# DetectionPart.net
KiCad netlist of a schematic drawn in Altium Designer
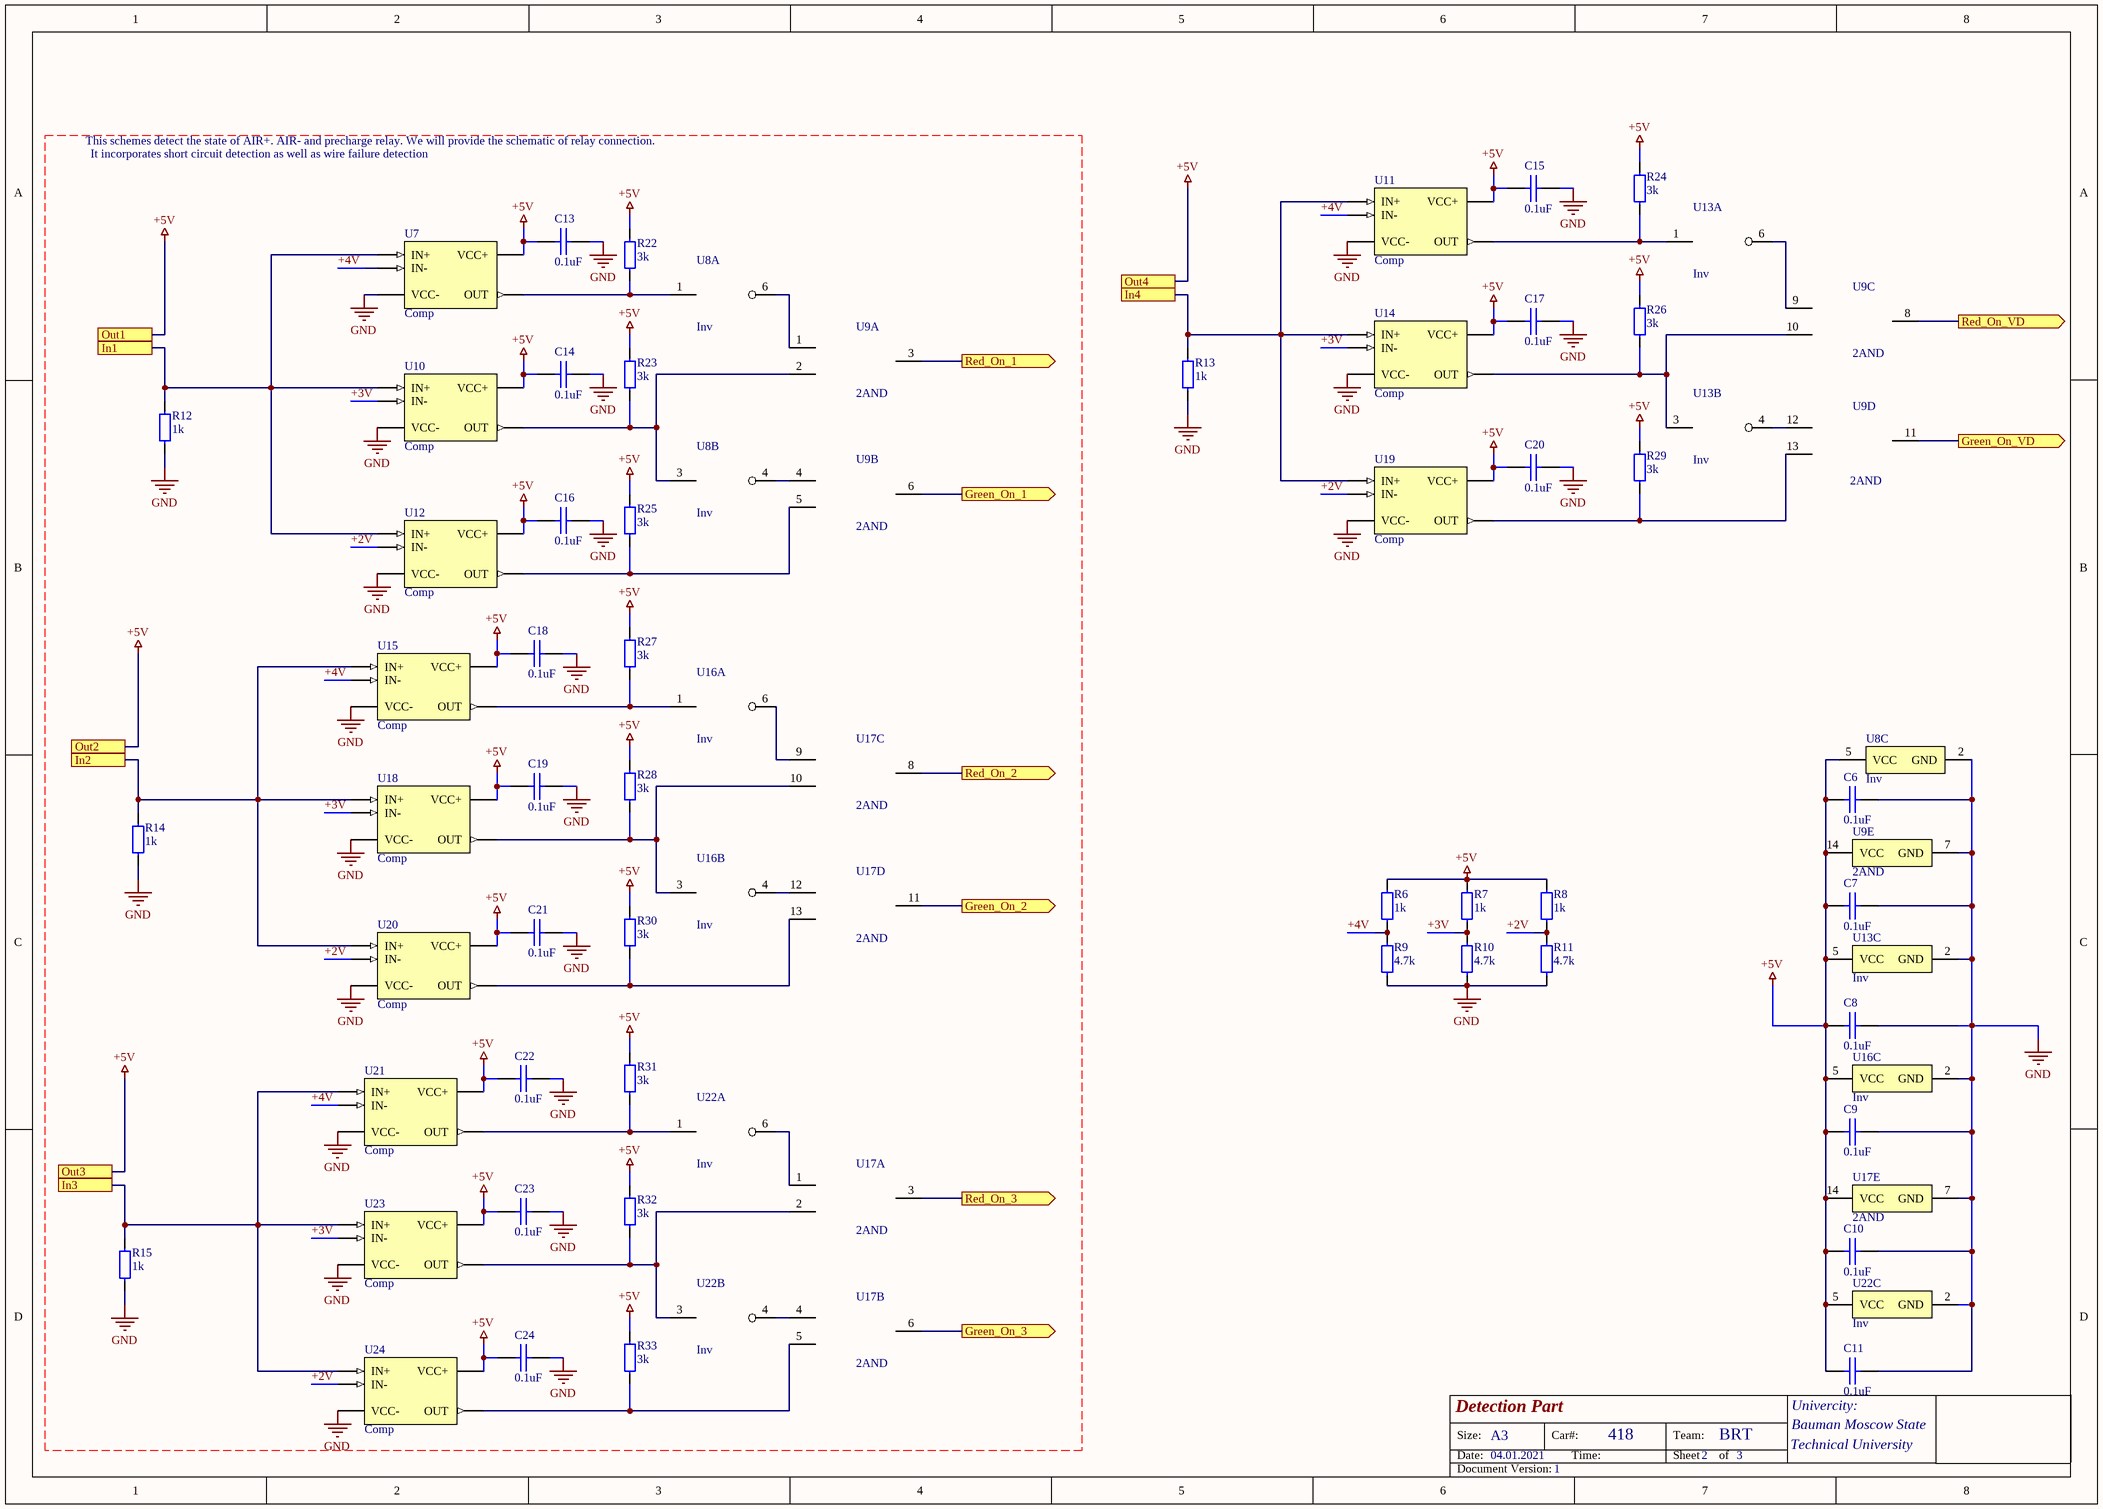
[diagram p0: DetectionPart.SchDoc]

(export (version "E")
  (design (tool "Eeschema 10.0.6"))
  (components
    (comp (ref "C6")
      (value "0.1uF")
      (footprint "0603 Capicator")
      (description "0.1uF X7R 16V 10% 0603")
      (fields
        (field (name "MANUFACTURER") "Murata Manufacturing")
        (field (name "PART NUMBER") "GRM188R71C104KA01D")
      )
      (libsource (lib "BRT_Components") (part "Cap 0.1uF (0603)"))
    )
    (comp (ref "C7")
      (value "0.1uF")
      (footprint "0603 Capicator")
      (description "0.1uF X7R 16V 10% 0603")
      (fields
        (field (name "MANUFACTURER") "Murata Manufacturing")
        (field (name "PART NUMBER") "GRM188R71C104KA01D")
      )
      (libsource (lib "BRT_Components") (part "Cap 0.1uF (0603)"))
    )
    (comp (ref "C8")
      (value "0.1uF")
      (footprint "0603 Capicator")
      (description "0.1uF X7R 16V 10% 0603")
      (fields
        (field (name "MANUFACTURER") "Murata Manufacturing")
        (field (name "PART NUMBER") "GRM188R71C104KA01D")
      )
      (libsource (lib "BRT_Components") (part "Cap 0.1uF (0603)"))
    )
    (comp (ref "C9")
      (value "0.1uF")
      (footprint "0603 Capicator")
      (description "0.1uF X7R 16V 10% 0603")
      (fields
        (field (name "MANUFACTURER") "Murata Manufacturing")
        (field (name "PART NUMBER") "GRM188R71C104KA01D")
      )
      (libsource (lib "BRT_Components") (part "Cap 0.1uF (0603)"))
    )
    (comp (ref "C10")
      (value "0.1uF")
      (footprint "0603 Capicator")
      (description "0.1uF X7R 16V 10% 0603")
      (fields
        (field (name "MANUFACTURER") "Murata Manufacturing")
        (field (name "PART NUMBER") "GRM188R71C104KA01D")
      )
      (libsource (lib "BRT_Components") (part "Cap 0.1uF (0603)"))
    )
    (comp (ref "C11")
      (value "0.1uF")
      (footprint "0603 Capicator")
      (description "0.1uF X7R 16V 10% 0603")
      (fields
        (field (name "MANUFACTURER") "Murata Manufacturing")
        (field (name "PART NUMBER") "GRM188R71C104KA01D")
      )
      (libsource (lib "BRT_Components") (part "Cap 0.1uF (0603)"))
    )
    (comp (ref "C13")
      (value "0.1uF")
      (footprint "0603 Capicator")
      (description "0.1uF X7R 16V 10% 0603")
      (fields
        (field (name "MANUFACTURER") "Murata Manufacturing")
        (field (name "PART NUMBER") "GRM188R71C104KA01D")
      )
      (libsource (lib "BRT_Components") (part "Cap 0.1uF (0603)"))
    )
    (comp (ref "C14")
      (value "0.1uF")
      (footprint "0603 Capicator")
      (description "0.1uF X7R 16V 10% 0603")
      (fields
        (field (name "MANUFACTURER") "Murata Manufacturing")
        (field (name "PART NUMBER") "GRM188R71C104KA01D")
      )
      (libsource (lib "BRT_Components") (part "Cap 0.1uF (0603)"))
    )
    (comp (ref "C15")
      (value "0.1uF")
      (footprint "0603 Capicator")
      (description "0.1uF X7R 16V 10% 0603")
      (fields
        (field (name "MANUFACTURER") "Murata Manufacturing")
        (field (name "PART NUMBER") "GRM188R71C104KA01D")
      )
      (libsource (lib "BRT_Components") (part "Cap 0.1uF (0603)"))
    )
    (comp (ref "C16")
      (value "0.1uF")
      (footprint "0603 Capicator")
      (description "0.1uF X7R 16V 10% 0603")
      (fields
        (field (name "MANUFACTURER") "Murata Manufacturing")
        (field (name "PART NUMBER") "GRM188R71C104KA01D")
      )
      (libsource (lib "BRT_Components") (part "Cap 0.1uF (0603)"))
    )
    (comp (ref "C17")
      (value "0.1uF")
      (footprint "0603 Capicator")
      (description "0.1uF X7R 16V 10% 0603")
      (fields
        (field (name "MANUFACTURER") "Murata Manufacturing")
        (field (name "PART NUMBER") "GRM188R71C104KA01D")
      )
      (libsource (lib "BRT_Components") (part "Cap 0.1uF (0603)"))
    )
    (comp (ref "C18")
      (value "0.1uF")
      (footprint "0603 Capicator")
      (description "0.1uF X7R 16V 10% 0603")
      (fields
        (field (name "MANUFACTURER") "Murata Manufacturing")
        (field (name "PART NUMBER") "GRM188R71C104KA01D")
      )
      (libsource (lib "BRT_Components") (part "Cap 0.1uF (0603)"))
    )
    (comp (ref "C19")
      (value "0.1uF")
      (footprint "0603 Capicator")
      (description "0.1uF X7R 16V 10% 0603")
      (fields
        (field (name "MANUFACTURER") "Murata Manufacturing")
        (field (name "PART NUMBER") "GRM188R71C104KA01D")
      )
      (libsource (lib "BRT_Components") (part "Cap 0.1uF (0603)"))
    )
    (comp (ref "C20")
      (value "0.1uF")
      (footprint "0603 Capicator")
      (description "0.1uF X7R 16V 10% 0603")
      (fields
        (field (name "MANUFACTURER") "Murata Manufacturing")
        (field (name "PART NUMBER") "GRM188R71C104KA01D")
      )
      (libsource (lib "BRT_Components") (part "Cap 0.1uF (0603)"))
    )
    (comp (ref "C21")
      (value "0.1uF")
      (footprint "0603 Capicator")
      (description "0.1uF X7R 16V 10% 0603")
      (fields
        (field (name "MANUFACTURER") "Murata Manufacturing")
        (field (name "PART NUMBER") "GRM188R71C104KA01D")
      )
      (libsource (lib "BRT_Components") (part "Cap 0.1uF (0603)"))
    )
    (comp (ref "C22")
      (value "0.1uF")
      (footprint "0603 Capicator")
      (description "0.1uF X7R 16V 10% 0603")
      (fields
        (field (name "MANUFACTURER") "Murata Manufacturing")
        (field (name "PART NUMBER") "GRM188R71C104KA01D")
      )
      (libsource (lib "BRT_Components") (part "Cap 0.1uF (0603)"))
    )
    (comp (ref "C23")
      (value "0.1uF")
      (footprint "0603 Capicator")
      (description "0.1uF X7R 16V 10% 0603")
      (fields
        (field (name "MANUFACTURER") "Murata Manufacturing")
        (field (name "PART NUMBER") "GRM188R71C104KA01D")
      )
      (libsource (lib "BRT_Components") (part "Cap 0.1uF (0603)"))
    )
    (comp (ref "C24")
      (value "0.1uF")
      (footprint "0603 Capicator")
      (description "0.1uF X7R 16V 10% 0603")
      (fields
        (field (name "MANUFACTURER") "Murata Manufacturing")
        (field (name "PART NUMBER") "GRM188R71C104KA01D")
      )
      (libsource (lib "BRT_Components") (part "Cap 0.1uF (0603)"))
    )
    (comp (ref "R6")
      (value "1k")
      (footprint "0603 Resistor")
      (description "0.1W 0603 1k, 1%")
      (fields (field (name "PART NUMBER") "RC0603FR-071KL") (field (name "MANUFACTURER") "Taiwan"))
      (libsource (lib "BRT_Components") (part "Res 1k (0603)"))
    )
    (comp (ref "R7")
      (value "1k")
      (footprint "0603 Resistor")
      (description "0.1W 0603 1k, 1%")
      (fields (field (name "PART NUMBER") "RC0603FR-071KL") (field (name "MANUFACTURER") "Taiwan"))
      (libsource (lib "BRT_Components") (part "Res 1k (0603)"))
    )
    (comp (ref "R8")
      (value "1k")
      (footprint "0603 Resistor")
      (description "0.1W 0603 1k, 1%")
      (fields (field (name "PART NUMBER") "RC0603FR-071KL") (field (name "MANUFACTURER") "Taiwan"))
      (libsource (lib "BRT_Components") (part "Res 1k (0603)"))
    )
    (comp (ref "R9")
      (value "4.7k")
      (footprint "0603 Resistor")
      (description "0.1W 0603 4.7k, 1%")
      (fields (field (name "PART NUMBER") "RC0603FR-074K7L") (field (name "MANUFACTURER") "Taiwan"))
      (libsource (lib "BRT_Components") (part "Res 4.7k (0603)"))
    )
    (comp (ref "R10")
      (value "4.7k")
      (footprint "0603 Resistor")
      (description "0.1W 0603 4.7k, 1%")
      (fields (field (name "PART NUMBER") "RC0603FR-074K7L") (field (name "MANUFACTURER") "Taiwan"))
      (libsource (lib "BRT_Components") (part "Res 4.7k (0603)"))
    )
    (comp (ref "R11")
      (value "4.7k")
      (footprint "0603 Resistor")
      (description "0.1W 0603 4.7k, 1%")
      (fields (field (name "PART NUMBER") "RC0603FR-074K7L") (field (name "MANUFACTURER") "Taiwan"))
      (libsource (lib "BRT_Components") (part "Res 4.7k (0603)"))
    )
    (comp (ref "R12")
      (value "1k")
      (footprint "0603 Resistor")
      (description "0.1W 0603 1k, 1%")
      (fields (field (name "PART NUMBER") "RC0603FR-071KL") (field (name "MANUFACTURER") "Taiwan"))
      (libsource (lib "BRT_Components") (part "Res 1k (0603)"))
    )
    (comp (ref "R13")
      (value "1k")
      (footprint "0603 Resistor")
      (description "0.1W 0603 1k, 1%")
      (fields (field (name "PART NUMBER") "RC0603FR-071KL") (field (name "MANUFACTURER") "Taiwan"))
      (libsource (lib "BRT_Components") (part "Res 1k (0603)"))
    )
    (comp (ref "R14")
      (value "1k")
      (footprint "0603 Resistor")
      (description "0.1W 0603 1k, 1%")
      (fields (field (name "PART NUMBER") "RC0603FR-071KL") (field (name "MANUFACTURER") "Taiwan"))
      (libsource (lib "BRT_Components") (part "Res 1k (0603)"))
    )
    (comp (ref "R15")
      (value "1k")
      (footprint "0603 Resistor")
      (description "0.1W 0603 1k, 1%")
      (fields (field (name "PART NUMBER") "RC0603FR-071KL") (field (name "MANUFACTURER") "Taiwan"))
      (libsource (lib "BRT_Components") (part "Res 1k (0603)"))
    )
    (comp (ref "R22")
      (value "3k")
      (footprint "0603 Resistor")
      (description "0.1W 0603 3k, 1%")
      (fields (field (name "PART NUMBER") "RC0603FR-073KL") (field (name "MANUFACTURER") "Taiwan"))
      (libsource (lib "BRT_Components") (part "Res 3k (0603)"))
    )
    (comp (ref "R23")
      (value "3k")
      (footprint "0603 Resistor")
      (description "0.1W 0603 3k, 1%")
      (fields (field (name "PART NUMBER") "RC0603FR-073KL") (field (name "MANUFACTURER") "Taiwan"))
      (libsource (lib "BRT_Components") (part "Res 3k (0603)"))
    )
    (comp (ref "R24")
      (value "3k")
      (footprint "0603 Resistor")
      (description "0.1W 0603 3k, 1%")
      (fields (field (name "PART NUMBER") "RC0603FR-073KL") (field (name "MANUFACTURER") "Taiwan"))
      (libsource (lib "BRT_Components") (part "Res 3k (0603)"))
    )
    (comp (ref "R25")
      (value "3k")
      (footprint "0603 Resistor")
      (description "0.1W 0603 3k, 1%")
      (fields (field (name "PART NUMBER") "RC0603FR-073KL") (field (name "MANUFACTURER") "Taiwan"))
      (libsource (lib "BRT_Components") (part "Res 3k (0603)"))
    )
    (comp (ref "R26")
      (value "3k")
      (footprint "0603 Resistor")
      (description "0.1W 0603 3k, 1%")
      (fields (field (name "PART NUMBER") "RC0603FR-073KL") (field (name "MANUFACTURER") "Taiwan"))
      (libsource (lib "BRT_Components") (part "Res 3k (0603)"))
    )
    (comp (ref "R27")
      (value "3k")
      (footprint "0603 Resistor")
      (description "0.1W 0603 3k, 1%")
      (fields (field (name "PART NUMBER") "RC0603FR-073KL") (field (name "MANUFACTURER") "Taiwan"))
      (libsource (lib "BRT_Components") (part "Res 3k (0603)"))
    )
    (comp (ref "R28")
      (value "3k")
      (footprint "0603 Resistor")
      (description "0.1W 0603 3k, 1%")
      (fields (field (name "PART NUMBER") "RC0603FR-073KL") (field (name "MANUFACTURER") "Taiwan"))
      (libsource (lib "BRT_Components") (part "Res 3k (0603)"))
    )
    (comp (ref "R29")
      (value "3k")
      (footprint "0603 Resistor")
      (description "0.1W 0603 3k, 1%")
      (fields (field (name "PART NUMBER") "RC0603FR-073KL") (field (name "MANUFACTURER") "Taiwan"))
      (libsource (lib "BRT_Components") (part "Res 3k (0603)"))
    )
    (comp (ref "R30")
      (value "3k")
      (footprint "0603 Resistor")
      (description "0.1W 0603 3k, 1%")
      (fields (field (name "PART NUMBER") "RC0603FR-073KL") (field (name "MANUFACTURER") "Taiwan"))
      (libsource (lib "BRT_Components") (part "Res 3k (0603)"))
    )
    (comp (ref "R31")
      (value "3k")
      (footprint "0603 Resistor")
      (description "0.1W 0603 3k, 1%")
      (fields (field (name "PART NUMBER") "RC0603FR-073KL") (field (name "MANUFACTURER") "Taiwan"))
      (libsource (lib "BRT_Components") (part "Res 3k (0603)"))
    )
    (comp (ref "R32")
      (value "3k")
      (footprint "0603 Resistor")
      (description "0.1W 0603 3k, 1%")
      (fields (field (name "PART NUMBER") "RC0603FR-073KL") (field (name "MANUFACTURER") "Taiwan"))
      (libsource (lib "BRT_Components") (part "Res 3k (0603)"))
    )
    (comp (ref "R33")
      (value "3k")
      (footprint "0603 Resistor")
      (description "0.1W 0603 3k, 1%")
      (fields (field (name "PART NUMBER") "RC0603FR-073KL") (field (name "MANUFACTURER") "Taiwan"))
      (libsource (lib "BRT_Components") (part "Res 3k (0603)"))
    )
    (comp (ref "U7")
      (value "Comp")
      (footprint "SOT-23-5")
      (description "Differential comparator with strobes")
      (fields (field (name "PART NUMBER") "LMV331M5/NOPB") (field (name "MANUFACTURER") "Texas Instruments"))
      (libsource (lib "BRT_Components") (part "Comparator [LMV]"))
    )
    (comp (ref "U8")
      (value "Inv")
      (footprint "SOT236")
      (description "Dual inverter, 1.65-5.5V")
      (fields
        (field (name "MANUFACTURER") "Texas Instruments")
        (field (name "PART NUMBER") "SN74LVC2G04DBVR")
      )
      (libsource (lib "BRT_Components") (part "Inverter (SN74)"))
    )
    (comp (ref "U9")
      (value "2AND")
      (footprint "SOIC-14")
      (description "4 logic elements \"2AND\"")
      (fields (field (name "PART NUMBER") "SN74AC08DR") (field (name "MANUFACTURER") "Texas Instruments"))
      (libsource (lib "BRT_Components") (part "2And"))
    )
    (comp (ref "U10")
      (value "Comp")
      (footprint "SOT-23-5")
      (description "Differential comparator with strobes")
      (fields (field (name "PART NUMBER") "LMV331M5/NOPB") (field (name "MANUFACTURER") "Texas Instruments"))
      (libsource (lib "BRT_Components") (part "Comparator [LMV]"))
    )
    (comp (ref "U11")
      (value "Comp")
      (footprint "SOT-23-5")
      (description "Differential comparator with strobes")
      (fields (field (name "PART NUMBER") "LMV331M5/NOPB") (field (name "MANUFACTURER") "Texas Instruments"))
      (libsource (lib "BRT_Components") (part "Comparator [LMV]"))
    )
    (comp (ref "U12")
      (value "Comp")
      (footprint "SOT-23-5")
      (description "Differential comparator with strobes")
      (fields (field (name "PART NUMBER") "LMV331M5/NOPB") (field (name "MANUFACTURER") "Texas Instruments"))
      (libsource (lib "BRT_Components") (part "Comparator [LMV]"))
    )
    (comp (ref "U13")
      (value "Inv")
      (footprint "SOT236")
      (description "Dual inverter, 1.65-5.5V")
      (fields
        (field (name "MANUFACTURER") "Texas Instruments")
        (field (name "PART NUMBER") "SN74LVC2G04DBVR")
      )
      (libsource (lib "BRT_Components") (part "Inverter (SN74)"))
    )
    (comp (ref "U14")
      (value "Comp")
      (footprint "SOT-23-5")
      (description "Differential comparator with strobes")
      (fields (field (name "PART NUMBER") "LMV331M5/NOPB") (field (name "MANUFACTURER") "Texas Instruments"))
      (libsource (lib "BRT_Components") (part "Comparator [LMV]"))
    )
    (comp (ref "U15")
      (value "Comp")
      (footprint "SOT-23-5")
      (description "Differential comparator with strobes")
      (fields (field (name "PART NUMBER") "LMV331M5/NOPB") (field (name "MANUFACTURER") "Texas Instruments"))
      (libsource (lib "BRT_Components") (part "Comparator [LMV]"))
    )
    (comp (ref "U16")
      (value "Inv")
      (footprint "SOT236")
      (description "Dual inverter, 1.65-5.5V")
      (fields
        (field (name "MANUFACTURER") "Texas Instruments")
        (field (name "PART NUMBER") "SN74LVC2G04DBVR")
      )
      (libsource (lib "BRT_Components") (part "Inverter (SN74)"))
    )
    (comp (ref "U17")
      (value "2AND")
      (footprint "SOIC-14")
      (description "4 logic elements \"2AND\"")
      (fields (field (name "PART NUMBER") "SN74AC08DR") (field (name "MANUFACTURER") "Texas Instruments"))
      (libsource (lib "BRT_Components") (part "2And"))
    )
    (comp (ref "U18")
      (value "Comp")
      (footprint "SOT-23-5")
      (description "Differential comparator with strobes")
      (fields (field (name "PART NUMBER") "LMV331M5/NOPB") (field (name "MANUFACTURER") "Texas Instruments"))
      (libsource (lib "BRT_Components") (part "Comparator [LMV]"))
    )
    (comp (ref "U19")
      (value "Comp")
      (footprint "SOT-23-5")
      (description "Differential comparator with strobes")
      (fields (field (name "PART NUMBER") "LMV331M5/NOPB") (field (name "MANUFACTURER") "Texas Instruments"))
      (libsource (lib "BRT_Components") (part "Comparator [LMV]"))
    )
    (comp (ref "U20")
      (value "Comp")
      (footprint "SOT-23-5")
      (description "Differential comparator with strobes")
      (fields (field (name "PART NUMBER") "LMV331M5/NOPB") (field (name "MANUFACTURER") "Texas Instruments"))
      (libsource (lib "BRT_Components") (part "Comparator [LMV]"))
    )
    (comp (ref "U21")
      (value "Comp")
      (footprint "SOT-23-5")
      (description "Differential comparator with strobes")
      (fields (field (name "PART NUMBER") "LMV331M5/NOPB") (field (name "MANUFACTURER") "Texas Instruments"))
      (libsource (lib "BRT_Components") (part "Comparator [LMV]"))
    )
    (comp (ref "U22")
      (value "Inv")
      (footprint "SOT236")
      (description "Dual inverter, 1.65-5.5V")
      (fields
        (field (name "MANUFACTURER") "Texas Instruments")
        (field (name "PART NUMBER") "SN74LVC2G04DBVR")
      )
      (libsource (lib "BRT_Components") (part "Inverter (SN74)"))
    )
    (comp (ref "U23")
      (value "Comp")
      (footprint "SOT-23-5")
      (description "Differential comparator with strobes")
      (fields (field (name "PART NUMBER") "LMV331M5/NOPB") (field (name "MANUFACTURER") "Texas Instruments"))
      (libsource (lib "BRT_Components") (part "Comparator [LMV]"))
    )
    (comp (ref "U24")
      (value "Comp")
      (footprint "SOT-23-5")
      (description "Differential comparator with strobes")
      (fields (field (name "PART NUMBER") "LMV331M5/NOPB") (field (name "MANUFACTURER") "Texas Instruments"))
      (libsource (lib "BRT_Components") (part "Comparator [LMV]"))
    )
  )
  (nets
    (net (code "1") (name "+5V") (class "Default")
      (node (ref "C10") (pin "2") (pinfunction "2_2") (pintype "passive"))
      (node (ref "C11") (pin "2") (pinfunction "2_2") (pintype "passive"))
      (node (ref "C13") (pin "2") (pinfunction "2_2") (pintype "passive"))
      (node (ref "C14") (pin "2") (pinfunction "2_2") (pintype "passive"))
      (node (ref "C15") (pin "2") (pinfunction "2_2") (pintype "passive"))
      (node (ref "C16") (pin "2") (pinfunction "2_2") (pintype "passive"))
      (node (ref "C17") (pin "2") (pinfunction "2_2") (pintype "passive"))
      (node (ref "C18") (pin "2") (pinfunction "2_2") (pintype "passive"))
      (node (ref "C19") (pin "2") (pinfunction "2_2") (pintype "passive"))
      (node (ref "C20") (pin "2") (pinfunction "2_2") (pintype "passive"))
      (node (ref "C21") (pin "2") (pinfunction "2_2") (pintype "passive"))
      (node (ref "C22") (pin "2") (pinfunction "2_2") (pintype "passive"))
      (node (ref "C23") (pin "2") (pinfunction "2_2") (pintype "passive"))
      (node (ref "C24") (pin "2") (pinfunction "2_2") (pintype "passive"))
      (node (ref "C6") (pin "1") (pinfunction "1_1") (pintype "passive"))
      (node (ref "C7") (pin "2") (pinfunction "2_2") (pintype "passive"))
      (node (ref "C8") (pin "2") (pinfunction "2_2") (pintype "passive"))
      (node (ref "C9") (pin "2") (pinfunction "2_2") (pintype "passive"))
      (node (ref "R22") (pin "2") (pinfunction "2_2") (pintype "passive"))
      (node (ref "R23") (pin "2") (pinfunction "2_2") (pintype "passive"))
      (node (ref "R24") (pin "2") (pinfunction "2_2") (pintype "passive"))
      (node (ref "R25") (pin "2") (pinfunction "2_2") (pintype "passive"))
      (node (ref "R26") (pin "2") (pinfunction "2_2") (pintype "passive"))
      (node (ref "R27") (pin "2") (pinfunction "2_2") (pintype "passive"))
      (node (ref "R28") (pin "2") (pinfunction "2_2") (pintype "passive"))
      (node (ref "R29") (pin "2") (pinfunction "2_2") (pintype "passive"))
      (node (ref "R30") (pin "2") (pinfunction "2_2") (pintype "passive"))
      (node (ref "R31") (pin "2") (pinfunction "2_2") (pintype "passive"))
      (node (ref "R32") (pin "2") (pinfunction "2_2") (pintype "passive"))
      (node (ref "R33") (pin "2") (pinfunction "2_2") (pintype "passive"))
      (node (ref "R6") (pin "2") (pinfunction "2_2") (pintype "passive"))
      (node (ref "R7") (pin "2") (pinfunction "2_2") (pintype "passive"))
      (node (ref "R8") (pin "2") (pinfunction "2_2") (pintype "passive"))
      (node (ref "U10") (pin "5") (pinfunction "VCC+_5") (pintype "power_in"))
      (node (ref "U11") (pin "5") (pinfunction "VCC+_5") (pintype "power_in"))
      (node (ref "U12") (pin "5") (pinfunction "VCC+_5") (pintype "power_in"))
      (node (ref "U13") (pin "5") (pinfunction "VCC_5") (pintype "power_in"))
      (node (ref "U14") (pin "5") (pinfunction "VCC+_5") (pintype "power_in"))
      (node (ref "U15") (pin "5") (pinfunction "VCC+_5") (pintype "power_in"))
      (node (ref "U16") (pin "5") (pinfunction "VCC_5") (pintype "power_in"))
      (node (ref "U17") (pin "14") (pinfunction "VCC_14") (pintype "power_in"))
      (node (ref "U18") (pin "5") (pinfunction "VCC+_5") (pintype "power_in"))
      (node (ref "U19") (pin "5") (pinfunction "VCC+_5") (pintype "power_in"))
      (node (ref "U20") (pin "5") (pinfunction "VCC+_5") (pintype "power_in"))
      (node (ref "U21") (pin "5") (pinfunction "VCC+_5") (pintype "power_in"))
      (node (ref "U22") (pin "5") (pinfunction "VCC_5") (pintype "power_in"))
      (node (ref "U23") (pin "5") (pinfunction "VCC+_5") (pintype "power_in"))
      (node (ref "U24") (pin "5") (pinfunction "VCC+_5") (pintype "power_in"))
      (node (ref "U7") (pin "5") (pinfunction "VCC+_5") (pintype "power_in"))
      (node (ref "U8") (pin "5") (pinfunction "VCC_5") (pintype "power_in"))
      (node (ref "U9") (pin "14") (pinfunction "VCC_14") (pintype "power_in"))
    )
    (net (code "2") (name "/+2V") (class "Default")
      (node (ref "R11") (pin "2") (pinfunction "2_2") (pintype "passive"))
      (node (ref "R8") (pin "1") (pinfunction "1_1") (pintype "passive"))
      (node (ref "U12") (pin "3") (pinfunction "IN-_3") (pintype "input"))
      (node (ref "U19") (pin "3") (pinfunction "IN-_3") (pintype "input"))
      (node (ref "U20") (pin "3") (pinfunction "IN-_3") (pintype "input"))
      (node (ref "U24") (pin "3") (pinfunction "IN-_3") (pintype "input"))
    )
    (net (code "3") (name "/+3V") (class "Default")
      (node (ref "R10") (pin "2") (pinfunction "2_2") (pintype "passive"))
      (node (ref "R7") (pin "1") (pinfunction "1_1") (pintype "passive"))
      (node (ref "U10") (pin "3") (pinfunction "IN-_3") (pintype "input"))
      (node (ref "U14") (pin "3") (pinfunction "IN-_3") (pintype "input"))
      (node (ref "U18") (pin "3") (pinfunction "IN-_3") (pintype "input"))
      (node (ref "U23") (pin "3") (pinfunction "IN-_3") (pintype "input"))
    )
    (net (code "4") (name "/+4V") (class "Default")
      (node (ref "R6") (pin "1") (pinfunction "1_1") (pintype "passive"))
      (node (ref "R9") (pin "2") (pinfunction "2_2") (pintype "passive"))
      (node (ref "U11") (pin "3") (pinfunction "IN-_3") (pintype "input"))
      (node (ref "U15") (pin "3") (pinfunction "IN-_3") (pintype "input"))
      (node (ref "U21") (pin "3") (pinfunction "IN-_3") (pintype "input"))
      (node (ref "U7") (pin "3") (pinfunction "IN-_3") (pintype "input"))
    )
    (net (code "5") (name "/Green_On_1") (class "Default")
      (node (ref "U9") (pin "6") (pinfunction "2Y_6") (pintype "passive"))
    )
    (net (code "6") (name "/Green_On_2") (class "Default")
      (node (ref "U17") (pin "11") (pinfunction "4Y_11") (pintype "passive"))
    )
    (net (code "7") (name "/Green_On_3") (class "Default")
      (node (ref "U17") (pin "6") (pinfunction "2Y_6") (pintype "passive"))
    )
    (net (code "8") (name "/Green_On_VD") (class "Default")
      (node (ref "U9") (pin "11") (pinfunction "4Y_11") (pintype "passive"))
    )
    (net (code "9") (name "/In1") (class "Default")
      (node (ref "R12") (pin "2") (pinfunction "2_2") (pintype "passive"))
      (node (ref "U10") (pin "1") (pinfunction "IN+_1") (pintype "input"))
      (node (ref "U12") (pin "1") (pinfunction "IN+_1") (pintype "input"))
      (node (ref "U7") (pin "1") (pinfunction "IN+_1") (pintype "input"))
    )
    (net (code "10") (name "/In2") (class "Default")
      (node (ref "R14") (pin "2") (pinfunction "2_2") (pintype "passive"))
      (node (ref "U15") (pin "1") (pinfunction "IN+_1") (pintype "input"))
      (node (ref "U18") (pin "1") (pinfunction "IN+_1") (pintype "input"))
      (node (ref "U20") (pin "1") (pinfunction "IN+_1") (pintype "input"))
    )
    (net (code "11") (name "/In3") (class "Default")
      (node (ref "R15") (pin "2") (pinfunction "2_2") (pintype "passive"))
      (node (ref "U21") (pin "1") (pinfunction "IN+_1") (pintype "input"))
      (node (ref "U23") (pin "1") (pinfunction "IN+_1") (pintype "input"))
      (node (ref "U24") (pin "1") (pinfunction "IN+_1") (pintype "input"))
    )
    (net (code "12") (name "/In4") (class "Default")
      (node (ref "R13") (pin "2") (pinfunction "2_2") (pintype "passive"))
      (node (ref "U11") (pin "1") (pinfunction "IN+_1") (pintype "input"))
      (node (ref "U14") (pin "1") (pinfunction "IN+_1") (pintype "input"))
      (node (ref "U19") (pin "1") (pinfunction "IN+_1") (pintype "input"))
    )
    (net (code "13") (name "/Red_On_1") (class "Default")
      (node (ref "U9") (pin "3") (pinfunction "1Y_3") (pintype "passive"))
    )
    (net (code "14") (name "/Red_On_2") (class "Default")
      (node (ref "U17") (pin "8") (pinfunction "3Y_8") (pintype "passive"))
    )
    (net (code "15") (name "/Red_On_3") (class "Default")
      (node (ref "U17") (pin "3") (pinfunction "1Y_3") (pintype "passive"))
    )
    (net (code "16") (name "/Red_On_VD") (class "Default")
      (node (ref "U9") (pin "8") (pinfunction "3Y_8") (pintype "passive"))
    )
    (net (code "17") (name "GND") (class "Default")
      (node (ref "C10") (pin "1") (pinfunction "1_1") (pintype "passive"))
      (node (ref "C11") (pin "1") (pinfunction "1_1") (pintype "passive"))
      (node (ref "C13") (pin "1") (pinfunction "1_1") (pintype "passive"))
      (node (ref "C14") (pin "1") (pinfunction "1_1") (pintype "passive"))
      (node (ref "C15") (pin "1") (pinfunction "1_1") (pintype "passive"))
      (node (ref "C16") (pin "1") (pinfunction "1_1") (pintype "passive"))
      (node (ref "C17") (pin "1") (pinfunction "1_1") (pintype "passive"))
      (node (ref "C18") (pin "1") (pinfunction "1_1") (pintype "passive"))
      (node (ref "C19") (pin "1") (pinfunction "1_1") (pintype "passive"))
      (node (ref "C20") (pin "1") (pinfunction "1_1") (pintype "passive"))
      (node (ref "C21") (pin "1") (pinfunction "1_1") (pintype "passive"))
      (node (ref "C22") (pin "1") (pinfunction "1_1") (pintype "passive"))
      (node (ref "C23") (pin "1") (pinfunction "1_1") (pintype "passive"))
      (node (ref "C24") (pin "1") (pinfunction "1_1") (pintype "passive"))
      (node (ref "C6") (pin "2") (pinfunction "2_2") (pintype "passive"))
      (node (ref "C7") (pin "1") (pinfunction "1_1") (pintype "passive"))
      (node (ref "C8") (pin "1") (pinfunction "1_1") (pintype "passive"))
      (node (ref "C9") (pin "1") (pinfunction "1_1") (pintype "passive"))
      (node (ref "R10") (pin "1") (pinfunction "1_1") (pintype "passive"))
      (node (ref "R11") (pin "1") (pinfunction "1_1") (pintype "passive"))
      (node (ref "R12") (pin "1") (pinfunction "1_1") (pintype "passive"))
      (node (ref "R13") (pin "1") (pinfunction "1_1") (pintype "passive"))
      (node (ref "R14") (pin "1") (pinfunction "1_1") (pintype "passive"))
      (node (ref "R15") (pin "1") (pinfunction "1_1") (pintype "passive"))
      (node (ref "R9") (pin "1") (pinfunction "1_1") (pintype "passive"))
      (node (ref "U10") (pin "2") (pinfunction "VCC-_2") (pintype "power_in"))
      (node (ref "U11") (pin "2") (pinfunction "VCC-_2") (pintype "power_in"))
      (node (ref "U12") (pin "2") (pinfunction "VCC-_2") (pintype "power_in"))
      (node (ref "U13") (pin "2") (pinfunction "GND_2") (pintype "power_in"))
      (node (ref "U14") (pin "2") (pinfunction "VCC-_2") (pintype "power_in"))
      (node (ref "U15") (pin "2") (pinfunction "VCC-_2") (pintype "power_in"))
      (node (ref "U16") (pin "2") (pinfunction "GND_2") (pintype "power_in"))
      (node (ref "U17") (pin "7") (pinfunction "GND_7") (pintype "power_in"))
      (node (ref "U18") (pin "2") (pinfunction "VCC-_2") (pintype "power_in"))
      (node (ref "U19") (pin "2") (pinfunction "VCC-_2") (pintype "power_in"))
      (node (ref "U20") (pin "2") (pinfunction "VCC-_2") (pintype "power_in"))
      (node (ref "U21") (pin "2") (pinfunction "VCC-_2") (pintype "power_in"))
      (node (ref "U22") (pin "2") (pinfunction "GND_2") (pintype "power_in"))
      (node (ref "U23") (pin "2") (pinfunction "VCC-_2") (pintype "power_in"))
      (node (ref "U24") (pin "2") (pinfunction "VCC-_2") (pintype "power_in"))
      (node (ref "U7") (pin "2") (pinfunction "VCC-_2") (pintype "power_in"))
      (node (ref "U8") (pin "2") (pinfunction "GND_2") (pintype "power_in"))
      (node (ref "U9") (pin "7") (pinfunction "GND_7") (pintype "power_in"))
    )
    (net (code "18") (name "Net-(U7-OUT)") (class "Default")
      (node (ref "R22") (pin "1") (pinfunction "1_1") (pintype "passive"))
      (node (ref "U7") (pin "4") (pinfunction "OUT_4") (pintype "output"))
      (node (ref "U8") (pin "1") (pinfunction "1A_1") (pintype "passive"))
    )
    (net (code "19") (name "Net-(U8A-1Y)") (class "Default")
      (node (ref "U8") (pin "6") (pinfunction "1Y_6") (pintype "passive"))
      (node (ref "U9") (pin "1") (pinfunction "1A_1") (pintype "passive"))
    )
    (net (code "20") (name "Net-(U8B-2Y)") (class "Default")
      (node (ref "U8") (pin "4") (pinfunction "2Y_4") (pintype "passive"))
      (node (ref "U9") (pin "4") (pinfunction "2A_4") (pintype "passive"))
    )
    (net (code "21") (name "Net-(U10-OUT)") (class "Default")
      (node (ref "R23") (pin "1") (pinfunction "1_1") (pintype "passive"))
      (node (ref "U10") (pin "4") (pinfunction "OUT_4") (pintype "output"))
      (node (ref "U8") (pin "3") (pinfunction "2А_3") (pintype "passive"))
      (node (ref "U9") (pin "2") (pinfunction "1B_2") (pintype "passive"))
    )
    (net (code "22") (name "Net-(U11-OUT)") (class "Default")
      (node (ref "R24") (pin "1") (pinfunction "1_1") (pintype "passive"))
      (node (ref "U11") (pin "4") (pinfunction "OUT_4") (pintype "output"))
      (node (ref "U13") (pin "1") (pinfunction "1A_1") (pintype "passive"))
    )
    (net (code "23") (name "Net-(U12-OUT)") (class "Default")
      (node (ref "R25") (pin "1") (pinfunction "1_1") (pintype "passive"))
      (node (ref "U12") (pin "4") (pinfunction "OUT_4") (pintype "output"))
      (node (ref "U9") (pin "5") (pinfunction "2B_5") (pintype "passive"))
    )
    (net (code "24") (name "Net-(U13A-1Y)") (class "Default")
      (node (ref "U13") (pin "6") (pinfunction "1Y_6") (pintype "passive"))
      (node (ref "U9") (pin "9") (pinfunction "3A_9") (pintype "passive"))
    )
    (net (code "25") (name "Net-(U13B-2Y)") (class "Default")
      (node (ref "U13") (pin "4") (pinfunction "2Y_4") (pintype "passive"))
      (node (ref "U9") (pin "12") (pinfunction "4A_12") (pintype "passive"))
    )
    (net (code "26") (name "Net-(U13B-2А)") (class "Default")
      (node (ref "R26") (pin "1") (pinfunction "1_1") (pintype "passive"))
      (node (ref "U13") (pin "3") (pinfunction "2А_3") (pintype "passive"))
      (node (ref "U14") (pin "4") (pinfunction "OUT_4") (pintype "output"))
      (node (ref "U9") (pin "10") (pinfunction "3B_10") (pintype "passive"))
    )
    (net (code "27") (name "Net-(U15-OUT)") (class "Default")
      (node (ref "R27") (pin "1") (pinfunction "1_1") (pintype "passive"))
      (node (ref "U15") (pin "4") (pinfunction "OUT_4") (pintype "output"))
      (node (ref "U16") (pin "1") (pinfunction "1A_1") (pintype "passive"))
    )
    (net (code "28") (name "Net-(U16A-1Y)") (class "Default")
      (node (ref "U16") (pin "6") (pinfunction "1Y_6") (pintype "passive"))
      (node (ref "U17") (pin "9") (pinfunction "3A_9") (pintype "passive"))
    )
    (net (code "29") (name "Net-(U16B-2Y)") (class "Default")
      (node (ref "U16") (pin "4") (pinfunction "2Y_4") (pintype "passive"))
      (node (ref "U17") (pin "12") (pinfunction "4A_12") (pintype "passive"))
    )
    (net (code "30") (name "Net-(U16B-2А)") (class "Default")
      (node (ref "R28") (pin "1") (pinfunction "1_1") (pintype "passive"))
      (node (ref "U16") (pin "3") (pinfunction "2А_3") (pintype "passive"))
      (node (ref "U17") (pin "10") (pinfunction "3B_10") (pintype "passive"))
      (node (ref "U18") (pin "4") (pinfunction "OUT_4") (pintype "output"))
    )
    (net (code "31") (name "Net-(U17A-1A)") (class "Default")
      (node (ref "U17") (pin "1") (pinfunction "1A_1") (pintype "passive"))
      (node (ref "U22") (pin "6") (pinfunction "1Y_6") (pintype "passive"))
    )
    (net (code "32") (name "Net-(U17A-1B)") (class "Default")
      (node (ref "R32") (pin "1") (pinfunction "1_1") (pintype "passive"))
      (node (ref "U17") (pin "2") (pinfunction "1B_2") (pintype "passive"))
      (node (ref "U22") (pin "3") (pinfunction "2А_3") (pintype "passive"))
      (node (ref "U23") (pin "4") (pinfunction "OUT_4") (pintype "output"))
    )
    (net (code "33") (name "Net-(U17B-2A)") (class "Default")
      (node (ref "U17") (pin "4") (pinfunction "2A_4") (pintype "passive"))
      (node (ref "U22") (pin "4") (pinfunction "2Y_4") (pintype "passive"))
    )
    (net (code "34") (name "Net-(U17B-2B)") (class "Default")
      (node (ref "R33") (pin "1") (pinfunction "1_1") (pintype "passive"))
      (node (ref "U17") (pin "5") (pinfunction "2B_5") (pintype "passive"))
      (node (ref "U24") (pin "4") (pinfunction "OUT_4") (pintype "output"))
    )
    (net (code "35") (name "Net-(U17D-4B)") (class "Default")
      (node (ref "R30") (pin "1") (pinfunction "1_1") (pintype "passive"))
      (node (ref "U17") (pin "13") (pinfunction "4B_13") (pintype "passive"))
      (node (ref "U20") (pin "4") (pinfunction "OUT_4") (pintype "output"))
    )
    (net (code "36") (name "Net-(U19-OUT)") (class "Default")
      (node (ref "R29") (pin "1") (pinfunction "1_1") (pintype "passive"))
      (node (ref "U19") (pin "4") (pinfunction "OUT_4") (pintype "output"))
      (node (ref "U9") (pin "13") (pinfunction "4B_13") (pintype "passive"))
    )
    (net (code "37") (name "Net-(U21-OUT)") (class "Default")
      (node (ref "R31") (pin "1") (pinfunction "1_1") (pintype "passive"))
      (node (ref "U21") (pin "4") (pinfunction "OUT_4") (pintype "output"))
      (node (ref "U22") (pin "1") (pinfunction "1A_1") (pintype "passive"))
    )
  )
)
